# T102.net
KiCad netlist of a schematic drawn in EAGLE
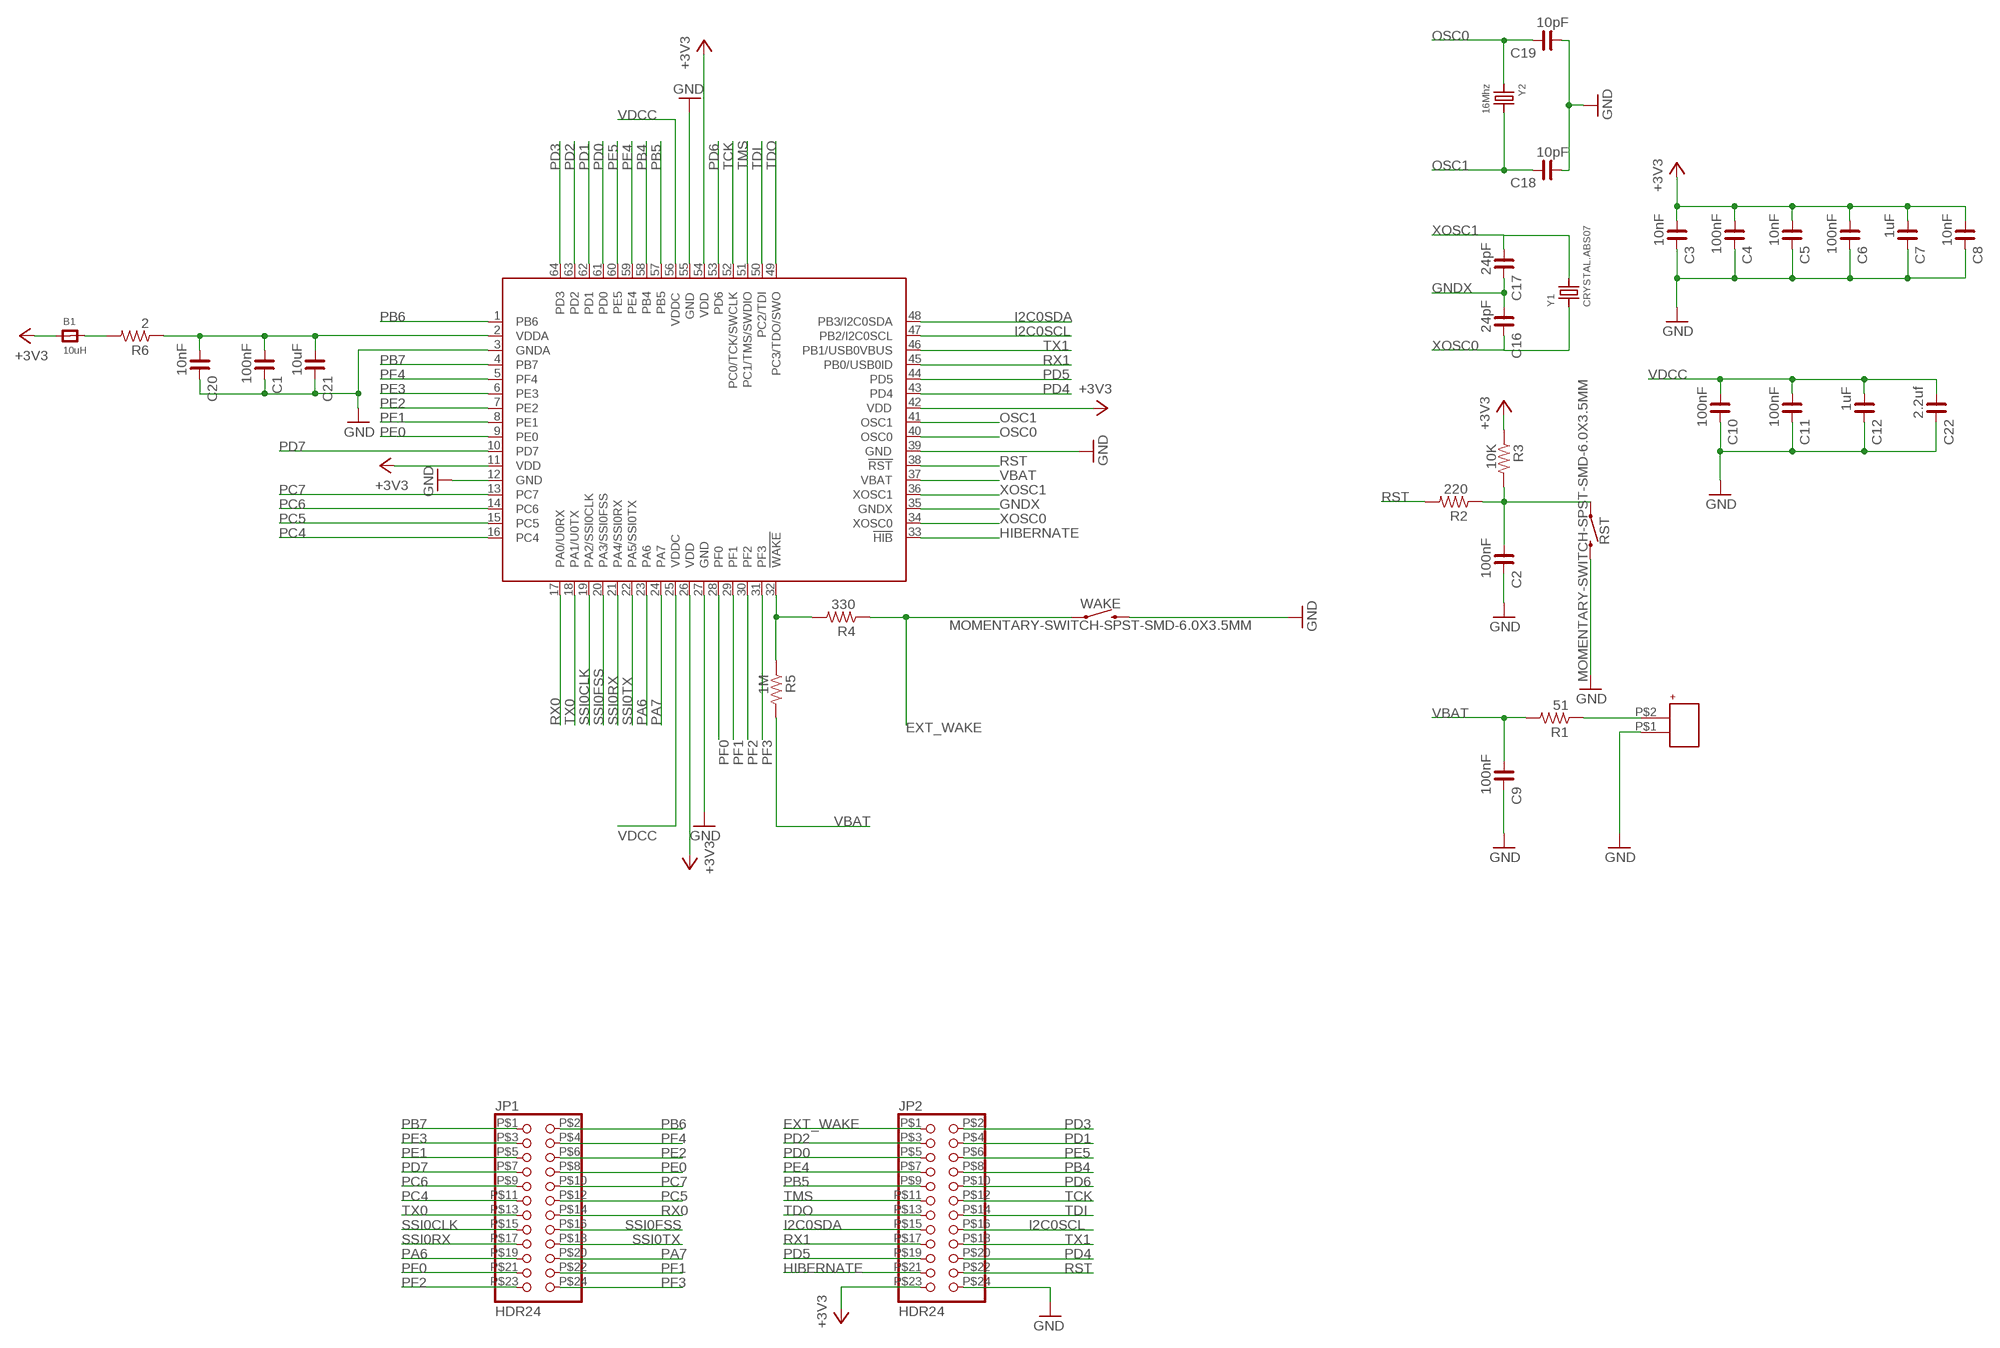
[diagram p0: schematic, sheet 1]

(export (version "E")
  (design (tool "Eeschema 10.0.6"))
  (components
    (comp (ref "B1")
      (value "10uH")
      (footprint "eagle-import:_0603")
      (libsource (lib "eagle-import") (part "FERRITE_0603"))
    )
    (comp (ref "C1")
      (value "100nF")
      (footprint "eagle-import:C0402")
      (libsource (lib "eagle-import") (part "C_0402"))
    )
    (comp (ref "C2")
      (value "100nF")
      (footprint "eagle-import:C0402")
      (libsource (lib "eagle-import") (part "C_0402"))
    )
    (comp (ref "C3")
      (value "10nF")
      (footprint "eagle-import:C0402")
      (libsource (lib "eagle-import") (part "C_0402"))
    )
    (comp (ref "C4")
      (value "100nF")
      (footprint "eagle-import:C0402")
      (libsource (lib "eagle-import") (part "C_0402"))
    )
    (comp (ref "C5")
      (value "10nF")
      (footprint "eagle-import:C0402")
      (libsource (lib "eagle-import") (part "C_0402"))
    )
    (comp (ref "C6")
      (value "100nF")
      (footprint "eagle-import:C0402")
      (libsource (lib "eagle-import") (part "C_0402"))
    )
    (comp (ref "C7")
      (value "1uF")
      (footprint "eagle-import:C0402")
      (libsource (lib "eagle-import") (part "C_0402"))
    )
    (comp (ref "C8")
      (value "10nF")
      (footprint "eagle-import:C0402")
      (libsource (lib "eagle-import") (part "C_0402"))
    )
    (comp (ref "C9")
      (value "100nF")
      (footprint "eagle-import:C0402")
      (libsource (lib "eagle-import") (part "C_0402"))
    )
    (comp (ref "C10")
      (value "100nF")
      (footprint "eagle-import:C0402")
      (libsource (lib "eagle-import") (part "C_0402"))
    )
    (comp (ref "C11")
      (value "100nF")
      (footprint "eagle-import:C0402")
      (libsource (lib "eagle-import") (part "C_0402"))
    )
    (comp (ref "C12")
      (value "1uF")
      (footprint "eagle-import:C0402")
      (libsource (lib "eagle-import") (part "C_0402"))
    )
    (comp (ref "C16")
      (value "24pF")
      (footprint "eagle-import:C0402")
      (libsource (lib "eagle-import") (part "C_0402"))
    )
    (comp (ref "C17")
      (value "24pF")
      (footprint "eagle-import:C0402")
      (libsource (lib "eagle-import") (part "C_0402"))
    )
    (comp (ref "C18")
      (value "10pF")
      (footprint "eagle-import:C0402")
      (libsource (lib "eagle-import") (part "C_0402"))
    )
    (comp (ref "C19")
      (value "10pF")
      (footprint "eagle-import:C0402")
      (libsource (lib "eagle-import") (part "C_0402"))
    )
    (comp (ref "C20")
      (value "10nF")
      (footprint "eagle-import:C0402")
      (libsource (lib "eagle-import") (part "C_0402"))
    )
    (comp (ref "C21")
      (value "10uF")
      (footprint "eagle-import:C0603")
      (libsource (lib "eagle-import") (part "C_0603"))
    )
    (comp (ref "C22")
      (value "2.2uf")
      (footprint "eagle-import:C0603")
      (libsource (lib "eagle-import") (part "C_0603"))
    )
    (comp (ref "IC1")
      (value "TM4C123[7,G]XXPM")
      (footprint "eagle-import:PM_S-PQFP-G64")
      (libsource (lib "eagle-import") (part "TM4C123[7,G]XXPM"))
    )
    (comp (ref "JP1")
      (value "HDR24")
      (footprint "eagle-import:HDR24")
      (libsource (lib "eagle-import") (part "HDR24"))
    )
    (comp (ref "JP2")
      (value "HDR24")
      (footprint "eagle-import:HDR24")
      (libsource (lib "eagle-import") (part "HDR24"))
    )
    (comp (ref "R1")
      (value "51")
      (footprint "eagle-import:R0402")
      (libsource (lib "eagle-import") (part "R_0402"))
    )
    (comp (ref "R2")
      (value "220")
      (footprint "eagle-import:R0402")
      (libsource (lib "eagle-import") (part "R_0402"))
    )
    (comp (ref "R3")
      (value "10K")
      (footprint "eagle-import:R0402")
      (libsource (lib "eagle-import") (part "R_0402"))
    )
    (comp (ref "R4")
      (value "330")
      (footprint "eagle-import:R0402")
      (libsource (lib "eagle-import") (part "R_0402"))
    )
    (comp (ref "R5")
      (value "1M")
      (footprint "eagle-import:R0402")
      (libsource (lib "eagle-import") (part "R_0402"))
    )
    (comp (ref "R6")
      (value "2")
      (footprint "eagle-import:R0402")
      (libsource (lib "eagle-import") (part "R_0402"))
    )
    (comp (ref "RST")
      (value "MOMENTARY-SWITCH-SPST-SMD-6.0X3.5MM")
      (footprint "eagle-import:TACTILE_SWITCH_SMD_6.0X3.5MM")
      (libsource (lib "eagle-import") (part "MOMENTARY-SWITCH-SPST-SMD-6.0X3.5MM"))
    )
    (comp (ref "U$1")
      (value "JST-MICROBAT")
      (footprint "eagle-import:JST-MICROBAT")
      (libsource (lib "eagle-import") (part "JST-MICROBAT"))
    )
    (comp (ref "WAKE")
      (value "MOMENTARY-SWITCH-SPST-SMD-6.0X3.5MM")
      (footprint "eagle-import:TACTILE_SWITCH_SMD_6.0X3.5MM")
      (libsource (lib "eagle-import") (part "MOMENTARY-SWITCH-SPST-SMD-6.0X3.5MM"))
    )
    (comp (ref "Y1")
      (value "CRYSTAL.ABS07")
      (footprint "eagle-import:ABS07")
      (libsource (lib "eagle-import") (part "CRYSTAL.ABS07"))
    )
    (comp (ref "Y2")
      (value "16Mhz")
      (footprint "eagle-import:6X3.3MM")
      (libsource (lib "eagle-import") (part "CRYSTAL.6X3.3MM"))
    )
  )
  (nets
    (net (code "1") (name "+3V3") (class "Default")
      (node (ref "B1") (pin "1") (pinfunction "P$1_1") (pintype "passive"))
      (node (ref "C3") (pin "1") (pinfunction "1_1") (pintype "passive"))
      (node (ref "C4") (pin "1") (pinfunction "1_1") (pintype "passive"))
      (node (ref "C5") (pin "1") (pinfunction "1_1") (pintype "passive"))
      (node (ref "C6") (pin "1") (pinfunction "1_1") (pintype "passive"))
      (node (ref "C7") (pin "1") (pinfunction "1_1") (pintype "passive"))
      (node (ref "C8") (pin "1") (pinfunction "1_1") (pintype "passive"))
      (node (ref "IC1") (pin "11") (pinfunction "VDD_11") (pintype "bidirectional"))
      (node (ref "IC1") (pin "26") (pinfunction "VDD_26") (pintype "bidirectional"))
      (node (ref "IC1") (pin "42") (pinfunction "VDD_42") (pintype "bidirectional"))
      (node (ref "IC1") (pin "54") (pinfunction "VDD_54") (pintype "bidirectional"))
      (node (ref "JP2") (pin "P$23") (pinfunction "23_P$23") (pintype "passive"))
      (node (ref "R3") (pin "1") (pinfunction "1_1") (pintype "passive"))
    )
    (net (code "2") (name "/EXT_WAKE") (class "Default")
      (node (ref "JP2") (pin "P$1") (pinfunction "1_P$1") (pintype "passive"))
      (node (ref "R4") (pin "1") (pinfunction "1_1") (pintype "passive"))
      (node (ref "WAKE") (pin "1") (pinfunction "1_1") (pintype "passive"))
    )
    (net (code "3") (name "/GNDX") (class "Default")
      (node (ref "C16") (pin "1") (pinfunction "1_1") (pintype "passive"))
      (node (ref "C17") (pin "2") (pinfunction "2_2") (pintype "passive"))
      (node (ref "IC1") (pin "35") (pinfunction "GNDX_35") (pintype "bidirectional"))
    )
    (net (code "4") (name "/HIBERNATE") (class "Default")
      (node (ref "IC1") (pin "33") (pinfunction "~{HIB}_33") (pintype "bidirectional"))
      (node (ref "JP2") (pin "P$21") (pinfunction "21_P$21") (pintype "passive"))
    )
    (net (code "5") (name "/I2C0SCL") (class "Default")
      (node (ref "IC1") (pin "47") (pinfunction "PB2/I2C0SCL_47") (pintype "bidirectional"))
      (node (ref "JP2") (pin "P$16") (pinfunction "16_P$16") (pintype "passive"))
    )
    (net (code "6") (name "/I2C0SDA") (class "Default")
      (node (ref "IC1") (pin "48") (pinfunction "PB3/I2C0SDA_48") (pintype "bidirectional"))
      (node (ref "JP2") (pin "P$15") (pinfunction "15_P$15") (pintype "passive"))
    )
    (net (code "7") (name "/OSC0") (class "Default")
      (node (ref "C19") (pin "2") (pinfunction "2_2") (pintype "passive"))
      (node (ref "IC1") (pin "40") (pinfunction "OSC0_40") (pintype "bidirectional"))
      (node (ref "Y2") (pin "1") (pinfunction "1_1") (pintype "passive"))
    )
    (net (code "8") (name "/OSC1") (class "Default")
      (node (ref "C18") (pin "2") (pinfunction "2_2") (pintype "passive"))
      (node (ref "IC1") (pin "41") (pinfunction "OSC1_41") (pintype "bidirectional"))
      (node (ref "Y2") (pin "2") (pinfunction "2_2") (pintype "passive"))
    )
    (net (code "9") (name "/PA6") (class "Default")
      (node (ref "IC1") (pin "23") (pinfunction "PA6_23") (pintype "bidirectional"))
      (node (ref "JP1") (pin "P$19") (pinfunction "19_P$19") (pintype "passive"))
    )
    (net (code "10") (name "/PA7") (class "Default")
      (node (ref "IC1") (pin "24") (pinfunction "PA7_24") (pintype "bidirectional"))
      (node (ref "JP1") (pin "P$20") (pinfunction "20_P$20") (pintype "passive"))
    )
    (net (code "11") (name "/PB4") (class "Default")
      (node (ref "IC1") (pin "58") (pinfunction "PB4_58") (pintype "bidirectional"))
      (node (ref "JP2") (pin "P$8") (pinfunction "8_P$8") (pintype "passive"))
    )
    (net (code "12") (name "/PB5") (class "Default")
      (node (ref "IC1") (pin "57") (pinfunction "PB5_57") (pintype "bidirectional"))
      (node (ref "JP2") (pin "P$9") (pinfunction "9_P$9") (pintype "passive"))
    )
    (net (code "13") (name "/PB6") (class "Default")
      (node (ref "IC1") (pin "1") (pinfunction "PB6_1") (pintype "bidirectional"))
      (node (ref "JP1") (pin "P$2") (pinfunction "2_P$2") (pintype "passive"))
    )
    (net (code "14") (name "/PB7") (class "Default")
      (node (ref "IC1") (pin "4") (pinfunction "PB7_4") (pintype "bidirectional"))
      (node (ref "JP1") (pin "P$1") (pinfunction "1_P$1") (pintype "passive"))
    )
    (net (code "15") (name "/PC4") (class "Default")
      (node (ref "IC1") (pin "16") (pinfunction "PC4_16") (pintype "bidirectional"))
      (node (ref "JP1") (pin "P$11") (pinfunction "11_P$11") (pintype "passive"))
    )
    (net (code "16") (name "/PC5") (class "Default")
      (node (ref "IC1") (pin "15") (pinfunction "PC5_15") (pintype "bidirectional"))
      (node (ref "JP1") (pin "P$12") (pinfunction "12_P$12") (pintype "passive"))
    )
    (net (code "17") (name "/PC6") (class "Default")
      (node (ref "IC1") (pin "14") (pinfunction "PC6_14") (pintype "bidirectional"))
      (node (ref "JP1") (pin "P$9") (pinfunction "9_P$9") (pintype "passive"))
    )
    (net (code "18") (name "/PC7") (class "Default")
      (node (ref "IC1") (pin "13") (pinfunction "PC7_13") (pintype "bidirectional"))
      (node (ref "JP1") (pin "P$10") (pinfunction "10_P$10") (pintype "passive"))
    )
    (net (code "19") (name "/PD0") (class "Default")
      (node (ref "IC1") (pin "61") (pinfunction "PD0_61") (pintype "bidirectional"))
      (node (ref "JP2") (pin "P$5") (pinfunction "5_P$5") (pintype "passive"))
    )
    (net (code "20") (name "/PD1") (class "Default")
      (node (ref "IC1") (pin "62") (pinfunction "PD1_62") (pintype "bidirectional"))
      (node (ref "JP2") (pin "P$4") (pinfunction "4_P$4") (pintype "passive"))
    )
    (net (code "21") (name "/PD2") (class "Default")
      (node (ref "IC1") (pin "63") (pinfunction "PD2_63") (pintype "bidirectional"))
      (node (ref "JP2") (pin "P$3") (pinfunction "3_P$3") (pintype "passive"))
    )
    (net (code "22") (name "/PD3") (class "Default")
      (node (ref "IC1") (pin "64") (pinfunction "PD3_64") (pintype "bidirectional"))
      (node (ref "JP2") (pin "P$2") (pinfunction "2_P$2") (pintype "passive"))
    )
    (net (code "23") (name "/PD4") (class "Default")
      (node (ref "IC1") (pin "43") (pinfunction "PD4_43") (pintype "bidirectional"))
      (node (ref "JP2") (pin "P$20") (pinfunction "20_P$20") (pintype "passive"))
    )
    (net (code "24") (name "/PD5") (class "Default")
      (node (ref "IC1") (pin "44") (pinfunction "PD5_44") (pintype "bidirectional"))
      (node (ref "JP2") (pin "P$19") (pinfunction "19_P$19") (pintype "passive"))
    )
    (net (code "25") (name "/PD6") (class "Default")
      (node (ref "IC1") (pin "53") (pinfunction "PD6_53") (pintype "bidirectional"))
      (node (ref "JP2") (pin "P$10") (pinfunction "10_P$10") (pintype "passive"))
    )
    (net (code "26") (name "/PD7") (class "Default")
      (node (ref "IC1") (pin "10") (pinfunction "PD7_10") (pintype "bidirectional"))
      (node (ref "JP1") (pin "P$7") (pinfunction "7_P$7") (pintype "passive"))
    )
    (net (code "27") (name "/PE0") (class "Default")
      (node (ref "IC1") (pin "9") (pinfunction "PE0_9") (pintype "bidirectional"))
      (node (ref "JP1") (pin "P$8") (pinfunction "8_P$8") (pintype "passive"))
    )
    (net (code "28") (name "/PE1") (class "Default")
      (node (ref "IC1") (pin "8") (pinfunction "PE1_8") (pintype "bidirectional"))
      (node (ref "JP1") (pin "P$5") (pinfunction "5_P$5") (pintype "passive"))
    )
    (net (code "29") (name "/PE2") (class "Default")
      (node (ref "IC1") (pin "7") (pinfunction "PE2_7") (pintype "bidirectional"))
      (node (ref "JP1") (pin "P$6") (pinfunction "6_P$6") (pintype "passive"))
    )
    (net (code "30") (name "/PE3") (class "Default")
      (node (ref "IC1") (pin "6") (pinfunction "PE3_6") (pintype "bidirectional"))
      (node (ref "JP1") (pin "P$3") (pinfunction "3_P$3") (pintype "passive"))
    )
    (net (code "31") (name "/PE4") (class "Default")
      (node (ref "IC1") (pin "59") (pinfunction "PE4_59") (pintype "bidirectional"))
      (node (ref "JP2") (pin "P$7") (pinfunction "7_P$7") (pintype "passive"))
    )
    (net (code "32") (name "/PE5") (class "Default")
      (node (ref "IC1") (pin "60") (pinfunction "PE5_60") (pintype "bidirectional"))
      (node (ref "JP2") (pin "P$6") (pinfunction "6_P$6") (pintype "passive"))
    )
    (net (code "33") (name "/PF0") (class "Default")
      (node (ref "IC1") (pin "28") (pinfunction "PF0_28") (pintype "bidirectional"))
      (node (ref "JP1") (pin "P$21") (pinfunction "21_P$21") (pintype "passive"))
    )
    (net (code "34") (name "/PF1") (class "Default")
      (node (ref "IC1") (pin "29") (pinfunction "PF1_29") (pintype "bidirectional"))
      (node (ref "JP1") (pin "P$22") (pinfunction "22_P$22") (pintype "passive"))
    )
    (net (code "35") (name "/PF2") (class "Default")
      (node (ref "IC1") (pin "30") (pinfunction "PF2_30") (pintype "bidirectional"))
      (node (ref "JP1") (pin "P$23") (pinfunction "23_P$23") (pintype "passive"))
    )
    (net (code "36") (name "/PF3") (class "Default")
      (node (ref "IC1") (pin "31") (pinfunction "PF3_31") (pintype "bidirectional"))
      (node (ref "JP1") (pin "P$24") (pinfunction "24_P$24") (pintype "passive"))
    )
    (net (code "37") (name "/PF4") (class "Default")
      (node (ref "IC1") (pin "5") (pinfunction "PF4_5") (pintype "bidirectional"))
      (node (ref "JP1") (pin "P$4") (pinfunction "4_P$4") (pintype "passive"))
    )
    (net (code "38") (name "/RST") (class "Default")
      (node (ref "IC1") (pin "38") (pinfunction "~{RST}_38") (pintype "bidirectional"))
      (node (ref "JP2") (pin "P$22") (pinfunction "22_P$22") (pintype "passive"))
      (node (ref "R2") (pin "2") (pinfunction "2_2") (pintype "passive"))
    )
    (net (code "39") (name "/RX0") (class "Default")
      (node (ref "IC1") (pin "17") (pinfunction "PA0/U0RX_17") (pintype "bidirectional"))
      (node (ref "JP1") (pin "P$14") (pinfunction "14_P$14") (pintype "passive"))
    )
    (net (code "40") (name "/RX1") (class "Default")
      (node (ref "IC1") (pin "45") (pinfunction "PB0/USB0ID_45") (pintype "bidirectional"))
      (node (ref "JP2") (pin "P$17") (pinfunction "17_P$17") (pintype "passive"))
    )
    (net (code "41") (name "/SSI0CLK") (class "Default")
      (node (ref "IC1") (pin "19") (pinfunction "PA2/SSI0CLK_19") (pintype "bidirectional"))
      (node (ref "JP1") (pin "P$15") (pinfunction "15_P$15") (pintype "passive"))
    )
    (net (code "42") (name "/SSI0FSS") (class "Default")
      (node (ref "IC1") (pin "20") (pinfunction "PA3/SSI0FSS_20") (pintype "bidirectional"))
      (node (ref "JP1") (pin "P$16") (pinfunction "16_P$16") (pintype "passive"))
    )
    (net (code "43") (name "/SSI0RX") (class "Default")
      (node (ref "IC1") (pin "21") (pinfunction "PA4/SSI0RX_21") (pintype "bidirectional"))
      (node (ref "JP1") (pin "P$17") (pinfunction "17_P$17") (pintype "passive"))
    )
    (net (code "44") (name "/SSI0TX") (class "Default")
      (node (ref "IC1") (pin "22") (pinfunction "PA5/SSI0TX_22") (pintype "bidirectional"))
      (node (ref "JP1") (pin "P$18") (pinfunction "18_P$18") (pintype "passive"))
    )
    (net (code "45") (name "/TCK") (class "Default")
      (node (ref "IC1") (pin "52") (pinfunction "PC0/TCK/SWCLK_52") (pintype "bidirectional"))
      (node (ref "JP2") (pin "P$12") (pinfunction "12_P$12") (pintype "passive"))
    )
    (net (code "46") (name "/TDI") (class "Default")
      (node (ref "IC1") (pin "50") (pinfunction "PC2/TDI_50") (pintype "bidirectional"))
      (node (ref "JP2") (pin "P$14") (pinfunction "14_P$14") (pintype "passive"))
    )
    (net (code "47") (name "/TDO") (class "Default")
      (node (ref "IC1") (pin "49") (pinfunction "PC3/TDO/SWO_49") (pintype "bidirectional"))
      (node (ref "JP2") (pin "P$13") (pinfunction "13_P$13") (pintype "passive"))
    )
    (net (code "48") (name "/TMS") (class "Default")
      (node (ref "IC1") (pin "51") (pinfunction "PC1/TMS/SWDIO_51") (pintype "bidirectional"))
      (node (ref "JP2") (pin "P$11") (pinfunction "11_P$11") (pintype "passive"))
    )
    (net (code "49") (name "/TX0") (class "Default")
      (node (ref "IC1") (pin "18") (pinfunction "PA1/U0TX_18") (pintype "bidirectional"))
      (node (ref "JP1") (pin "P$13") (pinfunction "13_P$13") (pintype "passive"))
    )
    (net (code "50") (name "/TX1") (class "Default")
      (node (ref "IC1") (pin "46") (pinfunction "PB1/USB0VBUS_46") (pintype "bidirectional"))
      (node (ref "JP2") (pin "P$18") (pinfunction "18_P$18") (pintype "passive"))
    )
    (net (code "51") (name "/VBAT") (class "Default")
      (node (ref "C9") (pin "1") (pinfunction "1_1") (pintype "passive"))
      (node (ref "IC1") (pin "37") (pinfunction "VBAT_37") (pintype "bidirectional"))
      (node (ref "R1") (pin "2") (pinfunction "2_2") (pintype "passive"))
      (node (ref "R5") (pin "2") (pinfunction "2_2") (pintype "passive"))
    )
    (net (code "52") (name "/VDCC") (class "Default")
      (node (ref "C10") (pin "1") (pinfunction "1_1") (pintype "passive"))
      (node (ref "C11") (pin "1") (pinfunction "1_1") (pintype "passive"))
      (node (ref "C12") (pin "1") (pinfunction "1_1") (pintype "passive"))
      (node (ref "C22") (pin "1") (pinfunction "1_1") (pintype "passive"))
      (node (ref "IC1") (pin "25") (pinfunction "VDDC_25") (pintype "bidirectional"))
      (node (ref "IC1") (pin "56") (pinfunction "VDDC_56") (pintype "bidirectional"))
    )
    (net (code "53") (name "/XOSC0") (class "Default")
      (node (ref "C16") (pin "2") (pinfunction "2_2") (pintype "passive"))
      (node (ref "IC1") (pin "34") (pinfunction "XOSC0_34") (pintype "bidirectional"))
      (node (ref "Y1") (pin "1") (pinfunction "1_1") (pintype "passive"))
    )
    (net (code "54") (name "/XOSC1") (class "Default")
      (node (ref "C17") (pin "1") (pinfunction "1_1") (pintype "passive"))
      (node (ref "IC1") (pin "36") (pinfunction "XOSC1_36") (pintype "bidirectional"))
      (node (ref "Y1") (pin "2") (pinfunction "2_2") (pintype "passive"))
    )
    (net (code "55") (name "GND") (class "Default")
      (node (ref "C1") (pin "2") (pinfunction "2_2") (pintype "passive"))
      (node (ref "C10") (pin "2") (pinfunction "2_2") (pintype "passive"))
      (node (ref "C11") (pin "2") (pinfunction "2_2") (pintype "passive"))
      (node (ref "C12") (pin "2") (pinfunction "2_2") (pintype "passive"))
      (node (ref "C18") (pin "1") (pinfunction "1_1") (pintype "passive"))
      (node (ref "C19") (pin "1") (pinfunction "1_1") (pintype "passive"))
      (node (ref "C2") (pin "2") (pinfunction "2_2") (pintype "passive"))
      (node (ref "C20") (pin "2") (pinfunction "2_2") (pintype "passive"))
      (node (ref "C21") (pin "2") (pinfunction "2_2") (pintype "passive"))
      (node (ref "C22") (pin "2") (pinfunction "2_2") (pintype "passive"))
      (node (ref "C3") (pin "2") (pinfunction "2_2") (pintype "passive"))
      (node (ref "C4") (pin "2") (pinfunction "2_2") (pintype "passive"))
      (node (ref "C5") (pin "2") (pinfunction "2_2") (pintype "passive"))
      (node (ref "C6") (pin "2") (pinfunction "2_2") (pintype "passive"))
      (node (ref "C7") (pin "2") (pinfunction "2_2") (pintype "passive"))
      (node (ref "C8") (pin "2") (pinfunction "2_2") (pintype "passive"))
      (node (ref "C9") (pin "2") (pinfunction "2_2") (pintype "passive"))
      (node (ref "IC1") (pin "12") (pinfunction "GND_12") (pintype "bidirectional"))
      (node (ref "IC1") (pin "27") (pinfunction "GND_27") (pintype "bidirectional"))
      (node (ref "IC1") (pin "3") (pinfunction "GNDA_3") (pintype "bidirectional"))
      (node (ref "IC1") (pin "39") (pinfunction "GND_39") (pintype "bidirectional"))
      (node (ref "IC1") (pin "55") (pinfunction "GND_55") (pintype "bidirectional"))
      (node (ref "JP2") (pin "P$24") (pinfunction "24_P$24") (pintype "passive"))
      (node (ref "RST") (pin "2") (pinfunction "2_2") (pintype "passive"))
      (node (ref "U$1") (pin "P$1") (pinfunction "P$1_P$1") (pintype "bidirectional"))
      (node (ref "WAKE") (pin "2") (pinfunction "2_2") (pintype "passive"))
    )
    (net (code "56") (name "Net-(B1-P$2)") (class "Default")
      (node (ref "B1") (pin "2") (pinfunction "P$2_2") (pintype "passive"))
      (node (ref "R6") (pin "2") (pinfunction "2_2") (pintype "passive"))
    )
    (net (code "57") (name "Net-(C2-Pad1)") (class "Default")
      (node (ref "C2") (pin "1") (pinfunction "1_1") (pintype "passive"))
      (node (ref "R2") (pin "1") (pinfunction "1_1") (pintype "passive"))
      (node (ref "R3") (pin "2") (pinfunction "2_2") (pintype "passive"))
      (node (ref "RST") (pin "1") (pinfunction "1_1") (pintype "passive"))
    )
    (net (code "58") (name "Net-(IC1-VDDA)") (class "Default")
      (node (ref "C1") (pin "1") (pinfunction "1_1") (pintype "passive"))
      (node (ref "C20") (pin "1") (pinfunction "1_1") (pintype "passive"))
      (node (ref "C21") (pin "1") (pinfunction "1_1") (pintype "passive"))
      (node (ref "IC1") (pin "2") (pinfunction "VDDA_2") (pintype "bidirectional"))
      (node (ref "R6") (pin "1") (pinfunction "1_1") (pintype "passive"))
    )
    (net (code "59") (name "Net-(IC1-~{WAKE})") (class "Default")
      (node (ref "IC1") (pin "32") (pinfunction "~{WAKE}_32") (pintype "bidirectional"))
      (node (ref "R4") (pin "2") (pinfunction "2_2") (pintype "passive"))
      (node (ref "R5") (pin "1") (pinfunction "1_1") (pintype "passive"))
    )
    (net (code "60") (name "Net-(R1-Pad1)") (class "Default")
      (node (ref "R1") (pin "1") (pinfunction "1_1") (pintype "passive"))
      (node (ref "U$1") (pin "P$2") (pinfunction "P$2_P$2") (pintype "bidirectional"))
    )
  )
)
